# sliding_protentiometer-v2_0.net
KiCad netlist of a schematic drawn in EAGLE
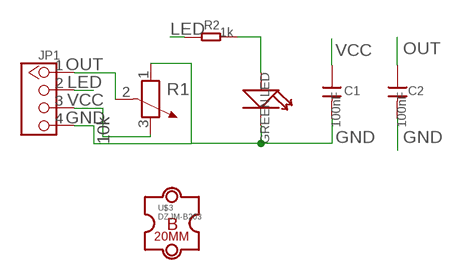
[diagram p0: schematic, sheet 1]

(export (version "E")
  (design (tool "Eeschema 10.0.6"))
  (components
    (comp (ref "C1")
      (value "100nF")
      (footprint "eagle-import:0805")
      (libsource (lib "eagle-import") (part "C-0805"))
    )
    (comp (ref "C2")
      (value "100nF")
      (footprint "eagle-import:0805")
      (libsource (lib "eagle-import") (part "C-0805"))
    )
    (comp (ref "JP1")
      (value "M0410")
      (footprint "eagle-import:JMZY-1X4")
      (libsource (lib "eagle-import") (part "M0410"))
    )
    (comp (ref "LED")
      (value "GREEN")
      (footprint "eagle-import:LED-0805")
      (libsource (lib "eagle-import") (part "LED'0805'"))
    )
    (comp (ref "R1")
      (value "10k")
      (footprint "eagle-import:3P-SQUA-45.6X10X5.8H")
      (libsource (lib "eagle-import") (part "R-POTENTIOMETER"))
    )
    (comp (ref "R2")
      (value "1k")
      (footprint "eagle-import:0805")
      (libsource (lib "eagle-import") (part "R-0805"))
    )
    (comp (ref "U$3")
      (value "DZJM-B203")
      (footprint "eagle-import:DZJM-B20-3P")
      (libsource (lib "eagle-import") (part "DZJM-B203"))
    )
  )
  (nets
    (net (code "1") (name "/GND") (class "Default")
      (node (ref "C1") (pin "2") (pinfunction "2_2") (pintype "passive"))
      (node (ref "C2") (pin "2") (pinfunction "2_2") (pintype "passive"))
      (node (ref "JP1") (pin "4") (pinfunction "P$4_4") (pintype "bidirectional"))
      (node (ref "LED") (pin "-") (pinfunction "-_-") (pintype "passive"))
      (node (ref "R1") (pin "1") (pinfunction "1_1") (pintype "passive"))
    )
    (net (code "2") (name "/LED") (class "Default")
      (node (ref "JP1") (pin "2") (pinfunction "P$2_2") (pintype "bidirectional"))
      (node (ref "R2") (pin "1") (pinfunction "1_1") (pintype "passive"))
    )
    (net (code "3") (name "/OUT") (class "Default")
      (node (ref "C2") (pin "1") (pinfunction "1_1") (pintype "passive"))
      (node (ref "JP1") (pin "1") (pinfunction "P$1_1") (pintype "bidirectional"))
      (node (ref "R1") (pin "2") (pinfunction "3_2") (pintype "passive"))
    )
    (net (code "4") (name "/VCC") (class "Default")
      (node (ref "C1") (pin "1") (pinfunction "1_1") (pintype "passive"))
      (node (ref "JP1") (pin "3") (pinfunction "P$3_3") (pintype "bidirectional"))
      (node (ref "R1") (pin "3") (pinfunction "2_3") (pintype "passive"))
    )
    (net (code "5") (name "Net-(LED-Pad+)") (class "Default")
      (node (ref "LED") (pin "+") (pinfunction "+_+") (pintype "passive"))
      (node (ref "R2") (pin "2") (pinfunction "2_2") (pintype "passive"))
    )
  )
)
